# IMUCubeCTRL_Sch.net
KiCad netlist of a schematic drawn in Altium Designer
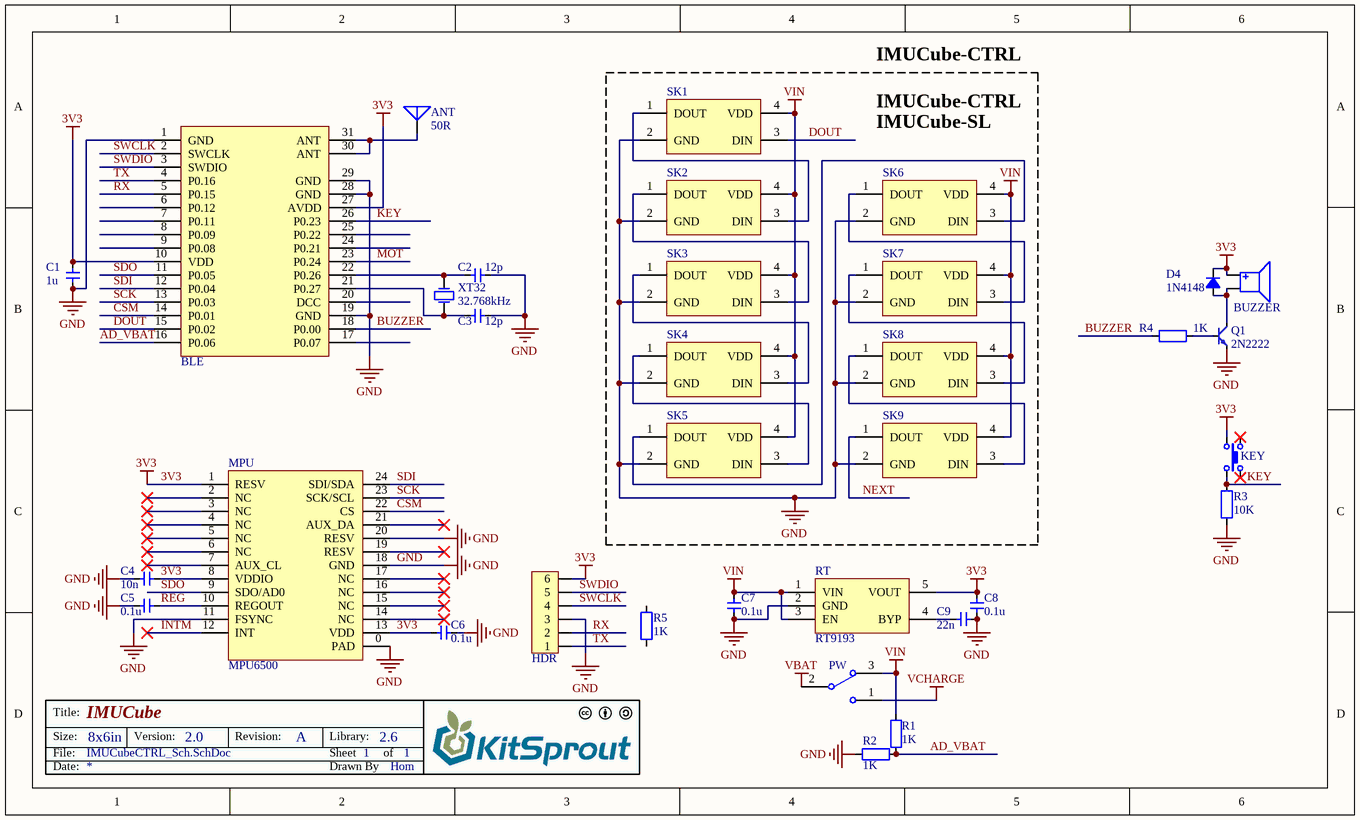
[diagram p0: IMUCubeCTRL_Sch.SchDoc]

(export (version "E")
  (design (tool "Eeschema 10.0.6"))
  (components
    (comp (ref "ANT")
      (value "50R")
      (footprint "PCB_Antenna:ANT_2.4G_3.2x1.6")
      (description "Antenna")
      (fields (field (name "Comment") "Ant_2.4G"))
      (libsource (lib "SCH_Antenna") (part "Ant_2.4G"))
    )
    (comp (ref "BLE")
      (value "MDBT40 nano")
      (footprint "PCB_Module:MDBT40 nano")
      (description "Module")
      (libsource (lib "SCH_Module") (part "MDBT40 nano"))
    )
    (comp (ref "BUZZER")
      (value "Buzzer")
      (footprint "PCB_Module:Buzzer_5x5")
      (libsource (lib "SCH_Module") (part "Buzzer"))
    )
    (comp (ref "C1")
      (value "1u")
      (footprint "PCB_PassiveCap:CAP_0402")
      (description "Capacitor")
      (fields (field (name "Comment") "Cap_0402"))
      (libsource (lib "SCH_Passive") (part "Cap_0402"))
    )
    (comp (ref "C2")
      (value "12p")
      (footprint "PCB_PassiveCap:CAP_0402")
      (description "Capacitor")
      (fields (field (name "Comment") "Cap_0402"))
      (libsource (lib "SCH_Passive") (part "Cap_0402"))
    )
    (comp (ref "C3")
      (value "12p")
      (footprint "PCB_PassiveCap:CAP_0402")
      (description "Capacitor")
      (fields (field (name "Comment") "Cap_0402"))
      (libsource (lib "SCH_Passive") (part "Cap_0402"))
    )
    (comp (ref "C4")
      (value "10n")
      (footprint "PCB_PassiveCap:CAP_0402")
      (description "Capacitor")
      (fields (field (name "Comment") "Cap_0402"))
      (libsource (lib "SCH_Passive") (part "Cap_0402"))
    )
    (comp (ref "C5")
      (value "0.1u")
      (footprint "PCB_PassiveCap:CAP_0402")
      (description "Capacitor")
      (fields (field (name "Comment") "Cap_0402"))
      (libsource (lib "SCH_Passive") (part "Cap_0402"))
    )
    (comp (ref "C6")
      (value "0.1u")
      (footprint "PCB_PassiveCap:CAP_0402")
      (description "Capacitor")
      (fields (field (name "Comment") "Cap_0402"))
      (libsource (lib "SCH_Passive") (part "Cap_0402"))
    )
    (comp (ref "C7")
      (value "0.1u")
      (footprint "PCB_PassiveCap:CAP_0402")
      (description "Capacitor")
      (fields (field (name "Comment") "Cap_0402"))
      (libsource (lib "SCH_Passive") (part "Cap_0402"))
    )
    (comp (ref "C8")
      (value "0.1u")
      (footprint "PCB_PassiveCap:CAP_0402")
      (description "Capacitor")
      (fields (field (name "Comment") "Cap_0402"))
      (libsource (lib "SCH_Passive") (part "Cap_0402"))
    )
    (comp (ref "C9")
      (value "22n")
      (footprint "PCB_PassiveCap:CAP_0402")
      (description "Capacitor")
      (fields (field (name "Comment") "Cap_0402"))
      (libsource (lib "SCH_Passive") (part "Cap_0402"))
    )
    (comp (ref "D4")
      (value "1N4148")
      (footprint "PCB_ActiveDIO:SOD-323")
      (description "Diode")
      (fields (field (name "Comment") "Diode_SOD323"))
      (libsource (lib "SCH_Active") (part "Diode_SOD323"))
    )
    (comp (ref "HDR")
      (value "HDR1x6_1.27")
      (footprint "PCB_ConnectorHDR:HDR1X6_1.27_180HFD")
      (description "Header")
      (libsource (lib "SCH_ConnectorHDR") (part "HDR1x6_1.27"))
    )
    (comp (ref "KEY")
      (value "ButtonTACT")
      (footprint "PCB_Switch:ButtonTACT_3.5*3.55_90")
      (description "Button")
      (libsource (lib "SCH_Switch") (part "ButtonTACT"))
    )
    (comp (ref "MPU")
      (value "MPU6500")
      (footprint "PCB_IntegratedCircuit:QFN_P0.4_24")
      (description "Sensor Motion")
      (libsource (lib "SCH_IntegratedCircuit") (part "MPU925x"))
    )
    (comp (ref "PW")
      (value "SwitchSPDT_2.8x6.6_90")
      (footprint "PCB_Switch:SwitchSPDT_2.8X6.6_90")
      (description "Switch")
      (libsource (lib "SCH_Switch") (part "SwitchSPDT_2.8x6.6_90"))
    )
    (comp (ref "Q1")
      (value "2N2222")
      (footprint "PCB_IntegratedCircuit:SOT23-3")
      (description "Transistor")
      (fields (field (name "Comment") "BJT_NPN"))
      (libsource (lib "SCH_Active") (part "BJT_NPN"))
    )
    (comp (ref "R1")
      (value "1K")
      (footprint "PCB_PassiveRes:RES_0402")
      (description "Resistor")
      (fields (field (name "Comment") "Res_0402"))
      (libsource (lib "") (part "Res_0402_1"))
    )
    (comp (ref "R2")
      (value "1K")
      (footprint "PCB_PassiveRes:RES_0402")
      (description "Resistor")
      (fields (field (name "Comment") "Res_0402"))
      (libsource (lib "SCH_Passive") (part "Res_0402"))
    )
    (comp (ref "R3")
      (value "10K")
      (footprint "PCB_PassiveRes:RES_0603")
      (description "Resistor")
      (fields (field (name "Comment") "Res_0603"))
      (libsource (lib "") (part "Res_0603_1"))
    )
    (comp (ref "R4")
      (value "1K")
      (footprint "PCB_PassiveRes:RES_0603")
      (description "Resistor")
      (fields (field (name "Comment") "Res_0603"))
      (libsource (lib "SCH_Passive") (part "Res_0603"))
    )
    (comp (ref "R5")
      (value "1K")
      (footprint "PCB_PassiveRes:RES_0402")
      (description "Resistor")
      (fields (field (name "Comment") "Res_0402"))
      (libsource (lib "") (part "Res_0402_2"))
    )
    (comp (ref "RT")
      (value "RT9193")
      (footprint "PCB_IntegratedCircuit:SOT23-5")
      (description "Power")
      (libsource (lib "SCH_IntegratedCircuit") (part "RT9193"))
    )
    (comp (ref "SK1")
      (value "LED_3535_SK6812")
      (footprint "PCB_ActiveLED:LED_3535_4P")
      (description "LED")
      (libsource (lib "SCH_Active") (part "LED_3535_SK6812"))
    )
    (comp (ref "SK2")
      (value "LED_3535_SK6812")
      (footprint "PCB_ActiveLED:LED_3535_4P")
      (description "LED")
      (libsource (lib "SCH_Active") (part "LED_3535_SK6812"))
    )
    (comp (ref "SK3")
      (value "LED_3535_SK6812")
      (footprint "PCB_ActiveLED:LED_3535_4P")
      (description "LED")
      (libsource (lib "SCH_Active") (part "LED_3535_SK6812"))
    )
    (comp (ref "SK4")
      (value "LED_3535_SK6812")
      (footprint "PCB_ActiveLED:LED_3535_4P")
      (description "LED")
      (libsource (lib "SCH_Active") (part "LED_3535_SK6812"))
    )
    (comp (ref "SK5")
      (value "LED_3535_SK6812")
      (footprint "PCB_ActiveLED:LED_3535_4P")
      (description "LED")
      (libsource (lib "SCH_Active") (part "LED_3535_SK6812"))
    )
    (comp (ref "SK6")
      (value "LED_3535_SK6812")
      (footprint "PCB_ActiveLED:LED_3535_4P")
      (description "LED")
      (libsource (lib "SCH_Active") (part "LED_3535_SK6812"))
    )
    (comp (ref "SK7")
      (value "LED_3535_SK6812")
      (footprint "PCB_ActiveLED:LED_3535_4P")
      (description "LED")
      (libsource (lib "SCH_Active") (part "LED_3535_SK6812"))
    )
    (comp (ref "SK8")
      (value "LED_3535_SK6812")
      (footprint "PCB_ActiveLED:LED_3535_4P")
      (description "LED")
      (libsource (lib "SCH_Active") (part "LED_3535_SK6812"))
    )
    (comp (ref "SK9")
      (value "LED_3535_SK6812")
      (footprint "PCB_ActiveLED:LED_3535_4P")
      (description "LED")
      (libsource (lib "SCH_Active") (part "LED_3535_SK6812"))
    )
    (comp (ref "XT32")
      (value "32.768kHz")
      (footprint "PCB_Oscillator:XT_2012_2")
      (description "Crystal Oscillator")
      (fields (field (name "Comment") "XTAL_32.768kHz"))
      (libsource (lib "SCH_Oscillator") (part "XTAL_32.768k"))
    )
  )
  (nets
    (net (code "1") (name "/AD_VBAT") (class "Default")
      (node (ref "BLE") (pin "16") (pinfunction "P0.06_16") (pintype "passive"))
      (node (ref "R1") (pin "2") (pinfunction "2_2") (pintype "passive"))
      (node (ref "R2") (pin "2") (pinfunction "2_2") (pintype "passive"))
    )
    (net (code "2") (name "/BUZZER") (class "Default")
      (node (ref "BLE") (pin "18") (pinfunction "P0.00_18") (pintype "passive"))
      (node (ref "R4") (pin "2") (pinfunction "2_2") (pintype "passive"))
    )
    (net (code "3") (name "/CSM") (class "Default")
      (node (ref "BLE") (pin "14") (pinfunction "P0.01_14") (pintype "passive"))
      (node (ref "MPU") (pin "22") (pinfunction "CS_22") (pintype "passive"))
    )
    (net (code "4") (name "/DOUT") (class "Default")
      (node (ref "BLE") (pin "15") (pinfunction "P0.02_15") (pintype "passive"))
      (node (ref "SK1") (pin "3") (pinfunction "DIN_3") (pintype "passive"))
    )
    (net (code "5") (name "/INTM") (class "Default")
      (node (ref "MPU") (pin "12") (pinfunction "INT_12") (pintype "passive+no_connect"))
    )
    (net (code "6") (name "/KEY") (class "Default")
      (node (ref "BLE") (pin "26") (pinfunction "P0.23_26") (pintype "passive"))
      (node (ref "KEY") (pin "4") (pinfunction "4_4") (pintype "passive"))
      (node (ref "R3") (pin "2") (pinfunction "2_2") (pintype "passive"))
    )
    (net (code "7") (name "/MOT") (class "Default")
      (node (ref "BLE") (pin "23") (pinfunction "P0.24_23") (pintype "passive"))
    )
    (net (code "8") (name "/NEXT") (class "Default")
      (node (ref "SK9") (pin "1") (pinfunction "DOUT_1") (pintype "passive"))
    )
    (net (code "9") (name "/REG") (class "Default")
      (node (ref "C5") (pin "2") (pinfunction "2_2") (pintype "passive"))
      (node (ref "MPU") (pin "10") (pinfunction "REGOUT_10") (pintype "passive"))
    )
    (net (code "10") (name "/RX") (class "Default")
      (node (ref "BLE") (pin "5") (pinfunction "P0.15_5") (pintype "passive"))
      (node (ref "HDR") (pin "2") (pinfunction "2_2") (pintype "passive"))
    )
    (net (code "11") (name "/SCK") (class "Default")
      (node (ref "BLE") (pin "13") (pinfunction "P0.03_13") (pintype "passive"))
      (node (ref "MPU") (pin "23") (pinfunction "SCK/SCL_23") (pintype "passive"))
    )
    (net (code "12") (name "/SDI") (class "Default")
      (node (ref "BLE") (pin "12") (pinfunction "P0.04_12") (pintype "passive"))
      (node (ref "MPU") (pin "24") (pinfunction "SDI/SDA_24") (pintype "passive"))
    )
    (net (code "13") (name "/SDO") (class "Default")
      (node (ref "BLE") (pin "11") (pinfunction "P0.05_11") (pintype "passive"))
      (node (ref "MPU") (pin "9") (pinfunction "SDO/AD0_9") (pintype "passive"))
    )
    (net (code "14") (name "/SWCLK") (class "Default")
      (node (ref "BLE") (pin "2") (pinfunction "SWCLK_2") (pintype "passive"))
      (node (ref "HDR") (pin "4") (pinfunction "4_4") (pintype "passive"))
    )
    (net (code "15") (name "/SWDIO") (class "Default")
      (node (ref "BLE") (pin "3") (pinfunction "SWDIO_3") (pintype "passive"))
      (node (ref "HDR") (pin "5") (pinfunction "5_5") (pintype "passive"))
    )
    (net (code "16") (name "/TX") (class "Default")
      (node (ref "BLE") (pin "4") (pinfunction "P0.16_4") (pintype "passive"))
      (node (ref "HDR") (pin "1") (pinfunction "1_1") (pintype "passive"))
    )
    (net (code "17") (name "3V3") (class "Default")
      (node (ref "BLE") (pin "10") (pinfunction "VDD_10") (pintype "passive"))
      (node (ref "BLE") (pin "27") (pinfunction "AVDD_27") (pintype "passive"))
      (node (ref "BUZZER") (pin "P") (pinfunction "Positive_P") (pintype "passive"))
      (node (ref "C1") (pin "2") (pinfunction "2_2") (pintype "passive"))
      (node (ref "C4") (pin "2") (pinfunction "2_2") (pintype "passive"))
      (node (ref "C6") (pin "2") (pinfunction "2_2") (pintype "passive"))
      (node (ref "C8") (pin "1") (pinfunction "1_1") (pintype "passive"))
      (node (ref "D4") (pin "2") (pinfunction "K_2") (pintype "passive"))
      (node (ref "HDR") (pin "6") (pinfunction "6_6") (pintype "passive"))
      (node (ref "KEY") (pin "3") (pinfunction "3_3") (pintype "passive"))
      (node (ref "MPU") (pin "1") (pinfunction "RESV_1") (pintype "passive"))
      (node (ref "MPU") (pin "13") (pinfunction "VDD_13") (pintype "passive"))
      (node (ref "MPU") (pin "8") (pinfunction "VDDIO_8") (pintype "passive"))
      (node (ref "RT") (pin "5") (pinfunction "VOUT_5") (pintype "passive"))
    )
    (net (code "18") (name "GND") (class "Default")
      (node (ref "BLE") (pin "1") (pinfunction "GND_1") (pintype "passive"))
      (node (ref "BLE") (pin "19") (pinfunction "GND_19") (pintype "passive"))
      (node (ref "BLE") (pin "28") (pinfunction "GND_28") (pintype "passive"))
      (node (ref "BLE") (pin "29") (pinfunction "GND_29") (pintype "passive"))
      (node (ref "C1") (pin "1") (pinfunction "1_1") (pintype "passive"))
      (node (ref "C2") (pin "2") (pinfunction "2_2") (pintype "passive"))
      (node (ref "C3") (pin "2") (pinfunction "2_2") (pintype "passive"))
      (node (ref "C4") (pin "1") (pinfunction "1_1") (pintype "passive"))
      (node (ref "C5") (pin "1") (pinfunction "1_1") (pintype "passive"))
      (node (ref "C6") (pin "1") (pinfunction "1_1") (pintype "passive"))
      (node (ref "C7") (pin "2") (pinfunction "2_2") (pintype "passive"))
      (node (ref "C8") (pin "2") (pinfunction "2_2") (pintype "passive"))
      (node (ref "C9") (pin "2") (pinfunction "2_2") (pintype "passive"))
      (node (ref "HDR") (pin "3") (pinfunction "3_3") (pintype "passive"))
      (node (ref "MPU") (pin "0") (pinfunction "PAD_0") (pintype "passive"))
      (node (ref "MPU") (pin "11") (pinfunction "FSYNC_11") (pintype "passive"))
      (node (ref "MPU") (pin "18") (pinfunction "GND_18") (pintype "passive"))
      (node (ref "MPU") (pin "20") (pinfunction "RESV_20") (pintype "passive"))
      (node (ref "Q1") (pin "2") (pinfunction "E_2") (pintype "passive"))
      (node (ref "R2") (pin "1") (pinfunction "1_1") (pintype "passive"))
      (node (ref "R3") (pin "1") (pinfunction "1_1") (pintype "passive"))
      (node (ref "RT") (pin "2") (pinfunction "GND_2") (pintype "passive"))
      (node (ref "SK1") (pin "2") (pinfunction "GND_2") (pintype "passive"))
      (node (ref "SK2") (pin "2") (pinfunction "GND_2") (pintype "passive"))
      (node (ref "SK3") (pin "2") (pinfunction "GND_2") (pintype "passive"))
      (node (ref "SK4") (pin "2") (pinfunction "GND_2") (pintype "passive"))
      (node (ref "SK5") (pin "2") (pinfunction "GND_2") (pintype "passive"))
      (node (ref "SK6") (pin "2") (pinfunction "GND_2") (pintype "passive"))
      (node (ref "SK7") (pin "2") (pinfunction "GND_2") (pintype "passive"))
      (node (ref "SK8") (pin "2") (pinfunction "GND_2") (pintype "passive"))
      (node (ref "SK9") (pin "2") (pinfunction "GND_2") (pintype "passive"))
    )
    (net (code "19") (name "Net-(ANT-A)") (class "Default")
      (node (ref "ANT") (pin "1") (pinfunction "A_1") (pintype "passive"))
      (node (ref "BLE") (pin "30") (pinfunction "ANT_30") (pintype "passive"))
      (node (ref "BLE") (pin "31") (pinfunction "ANT_31") (pintype "passive"))
    )
    (net (code "20") (name "Net-(BLE-P0.26)") (class "Default")
      (node (ref "BLE") (pin "22") (pinfunction "P0.26_22") (pintype "passive"))
      (node (ref "C2") (pin "1") (pinfunction "1_1") (pintype "passive"))
      (node (ref "XT32") (pin "2") (pinfunction "OSC2_2") (pintype "passive"))
    )
    (net (code "21") (name "Net-(BLE-P0.27)") (class "Default")
      (node (ref "BLE") (pin "21") (pinfunction "P0.27_21") (pintype "passive"))
      (node (ref "C3") (pin "1") (pinfunction "1_1") (pintype "passive"))
      (node (ref "XT32") (pin "1") (pinfunction "OSC1_1") (pintype "passive"))
    )
    (net (code "22") (name "Net-(BUZZER-Negative)") (class "Default")
      (node (ref "BUZZER") (pin "N") (pinfunction "Negative_N") (pintype "passive"))
      (node (ref "D4") (pin "1") (pinfunction "A_1") (pintype "passive"))
      (node (ref "Q1") (pin "3") (pinfunction "C_3") (pintype "passive"))
    )
    (net (code "23") (name "Net-(Q1-B)") (class "Default")
      (node (ref "Q1") (pin "1") (pinfunction "B_1") (pintype "passive"))
      (node (ref "R4") (pin "1") (pinfunction "1_1") (pintype "passive"))
    )
    (net (code "24") (name "Net-(RT-BYP)") (class "Default")
      (node (ref "C9") (pin "1") (pinfunction "1_1") (pintype "passive"))
      (node (ref "RT") (pin "4") (pinfunction "BYP_4") (pintype "passive"))
    )
    (net (code "25") (name "Net-(SK1-DOUT)") (class "Default")
      (node (ref "SK1") (pin "1") (pinfunction "DOUT_1") (pintype "passive"))
      (node (ref "SK2") (pin "3") (pinfunction "DIN_3") (pintype "passive"))
    )
    (net (code "26") (name "Net-(SK2-DOUT)") (class "Default")
      (node (ref "SK2") (pin "1") (pinfunction "DOUT_1") (pintype "passive"))
      (node (ref "SK3") (pin "3") (pinfunction "DIN_3") (pintype "passive"))
    )
    (net (code "27") (name "Net-(SK3-DOUT)") (class "Default")
      (node (ref "SK3") (pin "1") (pinfunction "DOUT_1") (pintype "passive"))
      (node (ref "SK4") (pin "3") (pinfunction "DIN_3") (pintype "passive"))
    )
    (net (code "28") (name "Net-(SK4-DOUT)") (class "Default")
      (node (ref "SK4") (pin "1") (pinfunction "DOUT_1") (pintype "passive"))
      (node (ref "SK5") (pin "3") (pinfunction "DIN_3") (pintype "passive"))
    )
    (net (code "29") (name "Net-(SK5-DOUT)") (class "Default")
      (node (ref "SK5") (pin "1") (pinfunction "DOUT_1") (pintype "passive"))
      (node (ref "SK6") (pin "3") (pinfunction "DIN_3") (pintype "passive"))
    )
    (net (code "30") (name "Net-(SK6-DOUT)") (class "Default")
      (node (ref "SK6") (pin "1") (pinfunction "DOUT_1") (pintype "passive"))
      (node (ref "SK7") (pin "3") (pinfunction "DIN_3") (pintype "passive"))
    )
    (net (code "31") (name "Net-(SK7-DOUT)") (class "Default")
      (node (ref "SK7") (pin "1") (pinfunction "DOUT_1") (pintype "passive"))
      (node (ref "SK8") (pin "3") (pinfunction "DIN_3") (pintype "passive"))
    )
    (net (code "32") (name "Net-(SK8-DOUT)") (class "Default")
      (node (ref "SK8") (pin "1") (pinfunction "DOUT_1") (pintype "passive"))
      (node (ref "SK9") (pin "3") (pinfunction "DIN_3") (pintype "passive"))
    )
    (net (code "33") (name "VBAT") (class "Default")
      (node (ref "PW") (pin "2") (pinfunction "2_2") (pintype "passive"))
    )
    (net (code "34") (name "VCHARGE") (class "Default")
      (node (ref "PW") (pin "1") (pinfunction "1_1") (pintype "passive"))
    )
    (net (code "35") (name "VIN") (class "Default")
      (node (ref "C7") (pin "1") (pinfunction "1_1") (pintype "passive"))
      (node (ref "PW") (pin "3") (pinfunction "3_3") (pintype "passive"))
      (node (ref "R1") (pin "1") (pinfunction "1_1") (pintype "passive"))
      (node (ref "RT") (pin "1") (pinfunction "VIN_1") (pintype "passive"))
      (node (ref "RT") (pin "3") (pinfunction "EN_3") (pintype "power_in"))
      (node (ref "SK1") (pin "4") (pinfunction "VDD_4") (pintype "passive"))
      (node (ref "SK2") (pin "4") (pinfunction "VDD_4") (pintype "passive"))
      (node (ref "SK3") (pin "4") (pinfunction "VDD_4") (pintype "passive"))
      (node (ref "SK4") (pin "4") (pinfunction "VDD_4") (pintype "passive"))
      (node (ref "SK5") (pin "4") (pinfunction "VDD_4") (pintype "passive"))
      (node (ref "SK6") (pin "4") (pinfunction "VDD_4") (pintype "passive"))
      (node (ref "SK7") (pin "4") (pinfunction "VDD_4") (pintype "passive"))
      (node (ref "SK8") (pin "4") (pinfunction "VDD_4") (pintype "passive"))
      (node (ref "SK9") (pin "4") (pinfunction "VDD_4") (pintype "passive"))
    )
    (net (code "36") (name "unconnected-(BLE-DCC-Pad20)") (class "Default")
      (node (ref "BLE") (pin "20") (pinfunction "DCC_20") (pintype "passive"))
    )
    (net (code "37") (name "unconnected-(BLE-P0.07-Pad17)") (class "Default")
      (node (ref "BLE") (pin "17") (pinfunction "P0.07_17") (pintype "passive"))
    )
    (net (code "38") (name "unconnected-(BLE-P0.08-Pad9)") (class "Default")
      (node (ref "BLE") (pin "9") (pinfunction "P0.08_9") (pintype "passive"))
    )
    (net (code "39") (name "unconnected-(BLE-P0.09-Pad8)") (class "Default")
      (node (ref "BLE") (pin "8") (pinfunction "P0.09_8") (pintype "passive"))
    )
    (net (code "40") (name "unconnected-(BLE-P0.11-Pad7)") (class "Default")
      (node (ref "BLE") (pin "7") (pinfunction "P0.11_7") (pintype "passive"))
    )
    (net (code "41") (name "unconnected-(BLE-P0.12-Pad6)") (class "Default")
      (node (ref "BLE") (pin "6") (pinfunction "P0.12_6") (pintype "passive"))
    )
    (net (code "42") (name "unconnected-(BLE-P0.21-Pad24)") (class "Default")
      (node (ref "BLE") (pin "24") (pinfunction "P0.21_24") (pintype "passive"))
    )
    (net (code "43") (name "unconnected-(BLE-P0.22-Pad25)") (class "Default")
      (node (ref "BLE") (pin "25") (pinfunction "P0.22_25") (pintype "passive"))
    )
    (net (code "44") (name "unconnected-(KEY-Pad1)") (class "Default")
      (node (ref "KEY") (pin "1") (pinfunction "1_1") (pintype "passive+no_connect"))
    )
    (net (code "45") (name "unconnected-(KEY-Pad2)") (class "Default")
      (node (ref "KEY") (pin "2") (pinfunction "2_2") (pintype "passive+no_connect"))
    )
    (net (code "46") (name "unconnected-(MPU-AUX_CL-Pad7)") (class "Default")
      (node (ref "MPU") (pin "7") (pinfunction "AUX_CL_7") (pintype "passive+no_connect"))
    )
    (net (code "47") (name "unconnected-(MPU-AUX_DA-Pad21)") (class "Default")
      (node (ref "MPU") (pin "21") (pinfunction "AUX_DA_21") (pintype "passive+no_connect"))
    )
    (net (code "48") (name "unconnected-(MPU-NC-Pad2)") (class "Default")
      (node (ref "MPU") (pin "2") (pinfunction "NC_2") (pintype "passive+no_connect"))
    )
    (net (code "49") (name "unconnected-(MPU-NC-Pad3)") (class "Default")
      (node (ref "MPU") (pin "3") (pinfunction "NC_3") (pintype "passive+no_connect"))
    )
    (net (code "50") (name "unconnected-(MPU-NC-Pad4)") (class "Default")
      (node (ref "MPU") (pin "4") (pinfunction "NC_4") (pintype "passive+no_connect"))
    )
    (net (code "51") (name "unconnected-(MPU-NC-Pad5)") (class "Default")
      (node (ref "MPU") (pin "5") (pinfunction "NC_5") (pintype "passive+no_connect"))
    )
    (net (code "52") (name "unconnected-(MPU-NC-Pad6)") (class "Default")
      (node (ref "MPU") (pin "6") (pinfunction "NC_6") (pintype "passive+no_connect"))
    )
    (net (code "53") (name "unconnected-(MPU-NC-Pad14)") (class "Default")
      (node (ref "MPU") (pin "14") (pinfunction "NC_14") (pintype "passive+no_connect"))
    )
    (net (code "54") (name "unconnected-(MPU-NC-Pad15)") (class "Default")
      (node (ref "MPU") (pin "15") (pinfunction "NC_15") (pintype "passive+no_connect"))
    )
    (net (code "55") (name "unconnected-(MPU-NC-Pad16)") (class "Default")
      (node (ref "MPU") (pin "16") (pinfunction "NC_16") (pintype "passive+no_connect"))
    )
    (net (code "56") (name "unconnected-(MPU-NC-Pad17)") (class "Default")
      (node (ref "MPU") (pin "17") (pinfunction "NC_17") (pintype "passive+no_connect"))
    )
    (net (code "57") (name "unconnected-(MPU-RESV-Pad19)") (class "Default")
      (node (ref "MPU") (pin "19") (pinfunction "RESV_19") (pintype "passive+no_connect"))
    )
    (net (code "58") (name "unconnected-(R5-Pad1)") (class "Default")
      (node (ref "R5") (pin "1") (pinfunction "1_1") (pintype "passive"))
    )
    (net (code "59") (name "unconnected-(R5-Pad2)") (class "Default")
      (node (ref "R5") (pin "2") (pinfunction "2_2") (pintype "passive"))
    )
  )
)
